# 04_USB.net
KiCad netlist of a schematic drawn in Altium Designer
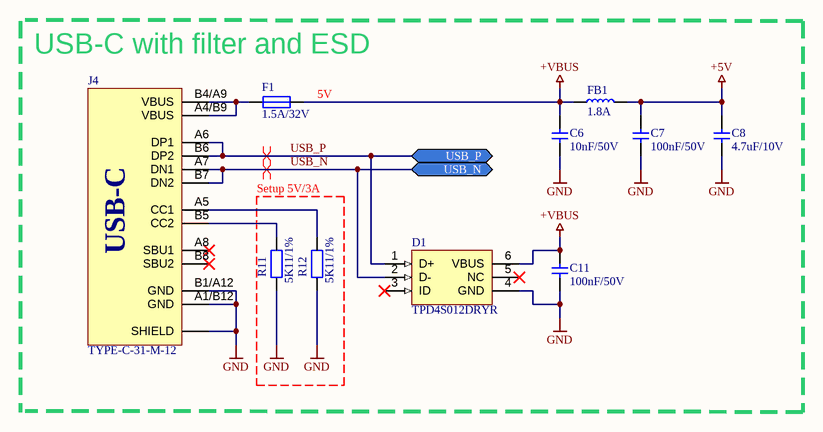
[diagram p0: 04 USB.SchDoc]

(export (version "E")
  (design (tool "Eeschema 10.0.6"))
  (components
    (comp (ref "C6")
      (value "10nF/50V")
      (footprint "CAPC1005X06N")
      (description "50V 10nF X7R ±10% 0402  Multilayer Ceramic Capacitors MLCC - SMD/SMT ROHS")
      (fields
        (field (name "MANUFACTURER") "Samsung Electro-Mechanics")
        (field (name "MFR_PART_NUMBER") "CL05B103KB5NNNC")
      )
      (libsource (lib "altium_symbol") (part "CL05B103KB5NNNC"))
    )
    (comp (ref "C7")
      (value "100nF/50V")
      (footprint "CAPC1005X06N")
      (description "16V 100nF X7R ±10% 0402  Multilayer Ceramic Capacitors MLCC - SMD/SMT ROHS")
      (fields
        (field (name "MANUFACTURER") "Samsung Electro-Mechanics")
        (field (name "MFR_PART_NUMBER") "CL05B104KO5NNNC")
      )
      (libsource (lib "altium_symbol") (part "CL05B104KO5NNNC"))
    )
    (comp (ref "C8")
      (value "4.7uF/10V")
      (footprint "CAPC1005X06N")
      (description "10V 4.7uF X5R ±20% 0402  Multilayer Ceramic Capacitors MLCC - SMD/SMT ROHS")
      (fields
        (field (name "MANUFACTURER") "Samsung Electro-Mechanics")
        (field (name "MFR_PART_NUMBER") "CL05A475MP5NRNC")
      )
      (libsource (lib "altium_symbol") (part "CL05A475MP5NRNC"))
    )
    (comp (ref "C11")
      (value "100nF/50V")
      (footprint "CAPC1005X06N")
      (description "16V 100nF X7R ±10% 0402  Multilayer Ceramic Capacitors MLCC - SMD/SMT ROHS")
      (fields
        (field (name "MANUFACTURER") "Samsung Electro-Mechanics")
        (field (name "MFR_PART_NUMBER") "CL05B104KO5NNNC")
      )
      (libsource (lib "altium_symbol") (part "CL05B104KO5NNNC"))
    )
    (comp (ref "D1")
      (value "TPD4S012DRYR")
      (footprint "SON50P100X60-6N")
      (description "3A 5.5V 6V Unidirectional SON-6  ESD Protection Devices ROHS")
      (fields (field (name "MANUFACTURER") "Texas Instruments"))
      (libsource (lib "altium_symbol") (part "TPD4S012DRYR"))
    )
    (comp (ref "F1")
      (value "1.5A/32V")
      (footprint "F0603HI1500V032T")
      (description "50A SMD Ceramic Fuse 1.5A 0.11 101mΩ 0603  Fuses ROHS")
      (fields (field (name "MANUFACTURER") "AEM") (field (name "MFR_PART_NUMBER") "F0603HI1500V032T"))
      (libsource (lib "altium_symbol") (part "F0603HI1500V032T"))
    )
    (comp (ref "FB1")
      (value "1.8A")
      (footprint "INDC1608X10N")
      (description "1.8A 1 60mΩ 30Ω@100MHz ±25% 0603  Ferrite Beads ROHS")
      (fields (field (name "MANUFACTURER") "Sunlord") (field (name "MFR_PART_NUMBER") "UPZ1608G300-1R8TF"))
      (libsource (lib "altium_symbol") (part "UPZ1608G300-1R8TF"))
    )
    (comp (ref "J4")
      (value "TYPE-C-31-M-12")
      (footprint "TYPE-C-31-M-12")
      (description "5A 1 16 Female Type-C SMD  USB Connectors ROHS")
      (fields (field (name "MANUFACTURER") "Korean Hroparts Elec"))
      (libsource (lib "altium_symbol") (part "TYPE-C-31-M-12"))
    )
    (comp (ref "R11")
      (value "5K11/1%")
      (footprint "RESC1005X04N")
      (description "62.5mW 50V ±1% ±200ppm/℃ -55℃~+155℃ 5.11kΩ 0402  Chip Resistor - Surface Mount ROHS")
      (fields
        (field (name "MANUFACTURER") "FH (Guangdong Fenghua Advanced Tech)")
        (field (name "MFR_PART_NUMBER") "RC-02W5111FT")
      )
      (libsource (lib "altium_symbol") (part "RC-02W5111FT"))
    )
    (comp (ref "R12")
      (value "5K11/1%")
      (footprint "RESC1005X04N")
      (description "62.5mW 50V ±1% ±200ppm/℃ -55℃~+155℃ 5.11kΩ 0402  Chip Resistor - Surface Mount ROHS")
      (fields
        (field (name "MANUFACTURER") "FH (Guangdong Fenghua Advanced Tech)")
        (field (name "MFR_PART_NUMBER") "RC-02W5111FT")
      )
      (libsource (lib "altium_symbol") (part "RC-02W5111FT"))
    )
  )
  (nets
    (net (code "1") (name "+5V") (class "Default")
      (node (ref "C7") (pin "2") (pinfunction "2_2") (pintype "passive"))
      (node (ref "C8") (pin "2") (pinfunction "2_2") (pintype "passive"))
      (node (ref "FB1") (pin "2") (pinfunction "2_2") (pintype "passive"))
    )
    (net (code "2") (name "+VBUS") (class "Default")
      (node (ref "C11") (pin "2") (pinfunction "2_2") (pintype "passive"))
      (node (ref "C6") (pin "2") (pinfunction "2_2") (pintype "passive"))
      (node (ref "D1") (pin "6") (pinfunction "VBUS_6") (pintype "passive"))
      (node (ref "F1") (pin "2") (pinfunction "2_2") (pintype "passive"))
      (node (ref "FB1") (pin "1") (pinfunction "1_1") (pintype "passive"))
    )
    (net (code "3") (name "/USB_N") (class "Default")
      (node (ref "D1") (pin "2") (pinfunction "D-_2") (pintype "input"))
      (node (ref "J4") (pin "A7") (pinfunction "DN1_A7") (pintype "passive"))
      (node (ref "J4") (pin "B7") (pinfunction "DN2_B7") (pintype "passive"))
    )
    (net (code "4") (name "/USB_P") (class "Default")
      (node (ref "D1") (pin "1") (pinfunction "D+_1") (pintype "input"))
      (node (ref "J4") (pin "A6") (pinfunction "DP1_A6") (pintype "passive"))
      (node (ref "J4") (pin "B6") (pinfunction "DP2_B6") (pintype "passive"))
    )
    (net (code "5") (name "GND") (class "Default")
      (node (ref "C11") (pin "1") (pinfunction "1_1") (pintype "passive"))
      (node (ref "C6") (pin "1") (pinfunction "1_1") (pintype "passive"))
      (node (ref "C7") (pin "1") (pinfunction "1_1") (pintype "passive"))
      (node (ref "C8") (pin "1") (pinfunction "1_1") (pintype "passive"))
      (node (ref "D1") (pin "4") (pinfunction "GND_4") (pintype "passive"))
      (node (ref "J4") (pin "A1/B12") (pinfunction "GND_A1/B12") (pintype "passive"))
      (node (ref "J4") (pin "B1/A12") (pinfunction "GND_B1/A12") (pintype "passive"))
      (node (ref "J4") (pin "SHIELD") (pinfunction "SHIELD_SHIELD") (pintype "passive"))
      (node (ref "R11") (pin "1") (pinfunction "1_1") (pintype "passive"))
      (node (ref "R12") (pin "1") (pinfunction "1_1") (pintype "passive"))
    )
    (net (code "6") (name "Net-(F1-Pad1)") (class "Default")
      (node (ref "F1") (pin "1") (pinfunction "1_1") (pintype "passive"))
      (node (ref "J4") (pin "A4/B9") (pinfunction "VBUS_A4/B9") (pintype "passive"))
      (node (ref "J4") (pin "B4/A9") (pinfunction "VBUS_B4/A9") (pintype "passive"))
    )
    (net (code "7") (name "Net-(J4-CC1)") (class "Default")
      (node (ref "J4") (pin "A5") (pinfunction "CC1_A5") (pintype "passive"))
      (node (ref "R12") (pin "2") (pinfunction "2_2") (pintype "passive"))
    )
    (net (code "8") (name "Net-(J4-CC2)") (class "Default")
      (node (ref "J4") (pin "B5") (pinfunction "CC2_B5") (pintype "passive"))
      (node (ref "R11") (pin "2") (pinfunction "2_2") (pintype "passive"))
    )
    (net (code "9") (name "unconnected-(D1-ID-Pad3)") (class "Default")
      (node (ref "D1") (pin "3") (pinfunction "ID_3") (pintype "input+no_connect"))
    )
    (net (code "10") (name "unconnected-(D1-NC-Pad5)") (class "Default")
      (node (ref "D1") (pin "5") (pinfunction "NC_5") (pintype "passive+no_connect"))
    )
    (net (code "11") (name "unconnected-(J4-SBU1-PadA8)") (class "Default")
      (node (ref "J4") (pin "A8") (pinfunction "SBU1_A8") (pintype "passive+no_connect"))
    )
    (net (code "12") (name "unconnected-(J4-SBU2-PadB8)") (class "Default")
      (node (ref "J4") (pin "B8") (pinfunction "SBU2_B8") (pintype "passive+no_connect"))
    )
  )
)
